# S3_CHAIR_SPKR-AMP_SPK.net
KiCad netlist of a schematic drawn in Altium Designer
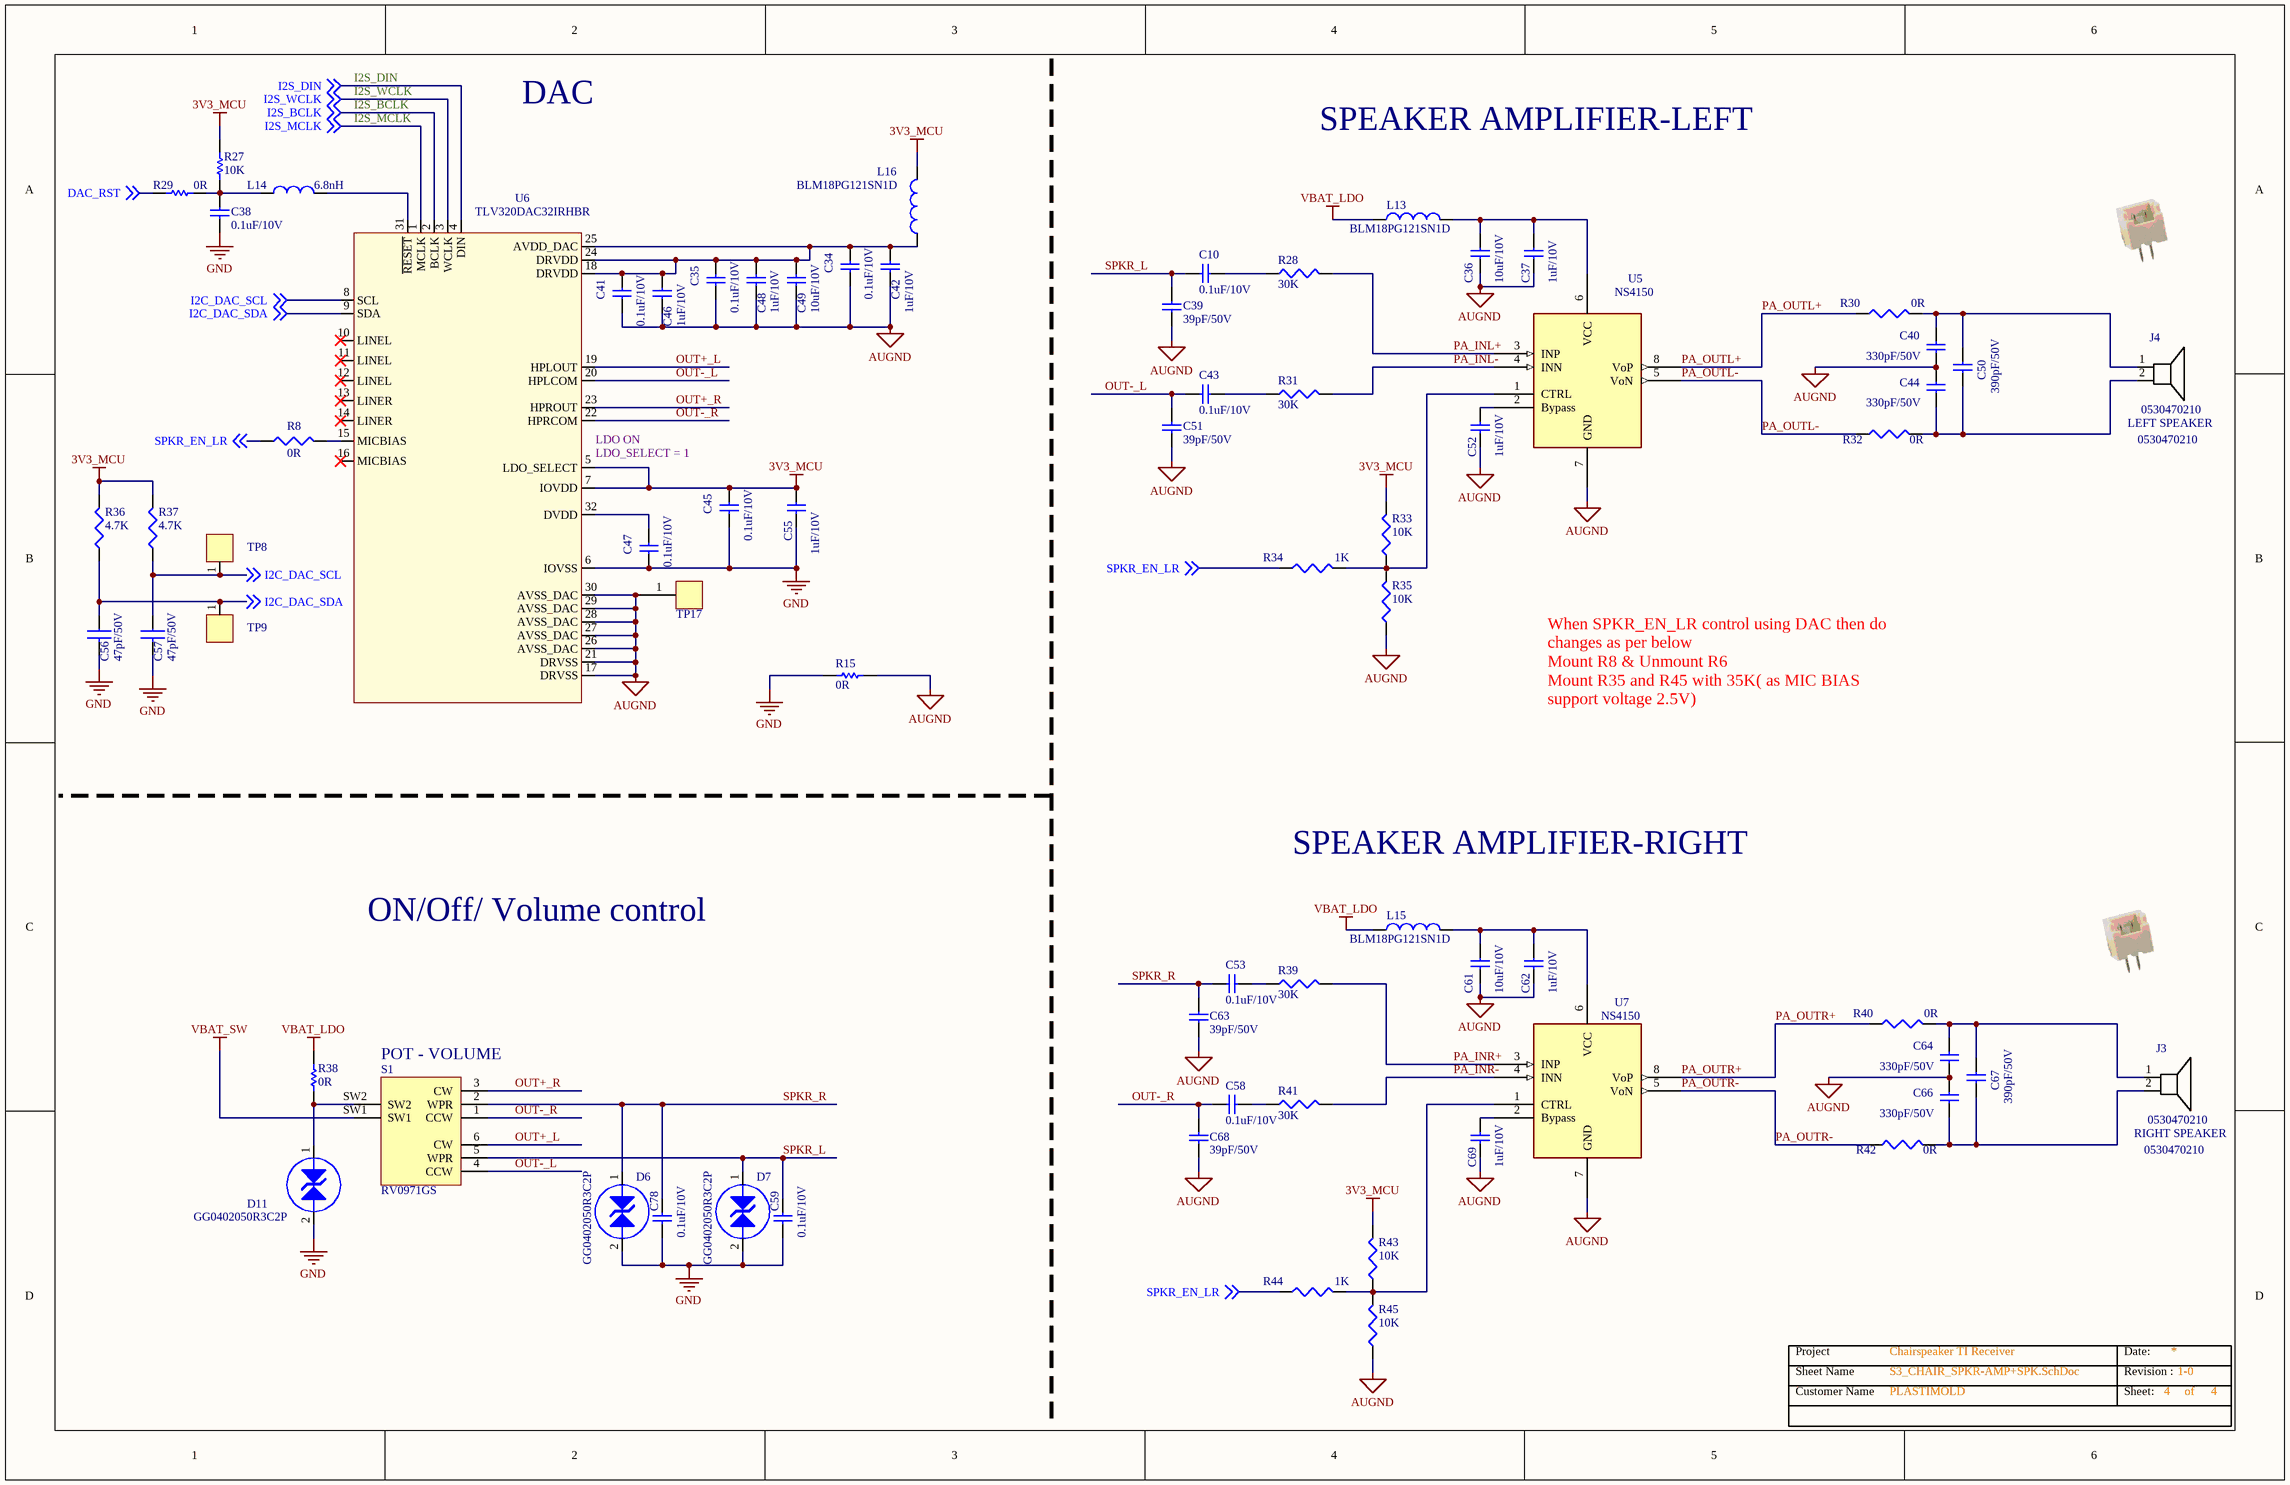
[diagram p0: S3_CHAIR_SPKR-AMP+SPK.SchDoc]

(export (version "E")
  (design (tool "Eeschema 10.0.6"))
  (components
    (comp (ref "C10")
      (value "0.1uF/10V")
      (footprint "CAP_0402_(M1005)")
      (description "=Description1")
      (libsource (lib "RC50_REV0-1_INT") (part "CAP_1"))
    )
    (comp (ref "C34")
      (value "0.1uF/10V")
      (footprint "CAP_0402_(M1005)")
      (description "=Description1")
      (libsource (lib "RC50_REV0-1_INT") (part "CAP_1"))
    )
    (comp (ref "C35")
      (value "0.1uF/10V")
      (footprint "CAP_0402_(M1005)")
      (description "=Description1")
      (libsource (lib "RC50_REV0-1_INT") (part "CAP_1"))
    )
    (comp (ref "C36")
      (value "10uF/10V")
      (footprint "CAP_0805_(M2012)")
      (description "=Description1")
      (libsource (lib "iTREE3") (part "CAP_10uF/16V_0805"))
    )
    (comp (ref "C37")
      (value "1uF/10V")
      (footprint "CAP_0402_(M1005)")
      (description "=Description1")
      (libsource (lib "iTREE3") (part "CAP_1uF/16v (10%)"))
    )
    (comp (ref "C38")
      (value "0.1uF/10V")
      (footprint "CAP_0402_(M1005)")
      (description "=Description1")
      (libsource (lib "RC50_REV0-1_INT") (part "CAP_1"))
    )
    (comp (ref "C39")
      (value "39pF/50V")
      (footprint "CAP_0402_(M1005)")
      (description "=Description1")
      (libsource (lib "iTREE3") (part "CAP_39pF/50V (±5%)"))
    )
    (comp (ref "C40")
      (value "330pF/50V")
      (footprint "CAP_0402_(M1005)")
      (description "=Description1")
      (libsource (lib "iTREE3") (part "CAP_330pF/50V (5%)"))
    )
    (comp (ref "C41")
      (value "0.1uF/10V")
      (footprint "CAP_0402_(M1005)")
      (description "=Description1")
      (libsource (lib "RC50_REV0-1_INT") (part "CAP_1"))
    )
    (comp (ref "C42")
      (value "1uF/10V")
      (footprint "CAP_0402_(M1005)")
      (description "=Description1")
      (libsource (lib "iTREE3") (part "CAP_1uF/16v (10%)"))
    )
    (comp (ref "C43")
      (value "0.1uF/10V")
      (footprint "CAP_0402_(M1005)")
      (description "=Description1")
      (libsource (lib "RC50_REV0-1_INT") (part "CAP_1"))
    )
    (comp (ref "C44")
      (value "330pF/50V")
      (footprint "CAP_0402_(M1005)")
      (description "=Description1")
      (libsource (lib "iTREE3") (part "CAP_330pF/50V (5%)"))
    )
    (comp (ref "C45")
      (value "0.1uF/10V")
      (footprint "CAP_0402_(M1005)")
      (description "=Description1")
      (libsource (lib "RC50_REV0-1_INT") (part "CAP_1"))
    )
    (comp (ref "C46")
      (value "1uF/10V")
      (footprint "CAP_0402_(M1005)")
      (description "=Description1")
      (libsource (lib "iTREE3") (part "CAP_1uF/16v (10%)"))
    )
    (comp (ref "C47")
      (value "0.1uF/10V")
      (footprint "CAP_0402_(M1005)")
      (description "=Description1")
      (libsource (lib "RC50_REV0-1_INT") (part "CAP_1"))
    )
    (comp (ref "C48")
      (value "1uF/10V")
      (footprint "CAP_0402_(M1005)")
      (description "=Description1")
      (libsource (lib "iTREE3") (part "CAP_1uF/16v (10%)"))
    )
    (comp (ref "C49")
      (value "10uF/10V")
      (footprint "CAP_0805_(M2012)")
      (description "=Description1")
      (libsource (lib "iTREE3") (part "CAP_10uF/16V_0805"))
    )
    (comp (ref "C50")
      (value "390pF/50V")
      (footprint "CAP_0402_(M1005)")
      (description "=Description1")
      (libsource (lib "iTREE3") (part "CAP_390pF/50V (5%)"))
    )
    (comp (ref "C51")
      (value "39pF/50V")
      (footprint "CAP_0402_(M1005)")
      (description "=Description1")
      (libsource (lib "iTREE3") (part "CAP_39pF/50V (±5%)"))
    )
    (comp (ref "C52")
      (value "1uF/10V")
      (footprint "CAP_0402_(M1005)")
      (description "=Description1")
      (libsource (lib "iTREE3") (part "CAP_1uF/16v (10%)"))
    )
    (comp (ref "C53")
      (value "0.1uF/10V")
      (footprint "CAP_0402_(M1005)")
      (description "=Description1")
      (libsource (lib "RC50_REV0-1_INT") (part "CAP_1"))
    )
    (comp (ref "C55")
      (value "1uF/10V")
      (footprint "CAP_0402_(M1005)")
      (description "=Description1")
      (libsource (lib "iTREE3") (part "CAP_1uF/16v (10%)"))
    )
    (comp (ref "C56")
      (value "47pF/50V")
      (footprint "CAP_0402_(M1005)")
      (description "=Description1")
      (libsource (lib "RC50_REV0-1") (part "CAP NP"))
    )
    (comp (ref "C57")
      (value "47pF/50V")
      (footprint "CAP_0402_(M1005)")
      (description "=Description1")
      (libsource (lib "RC50_REV0-1") (part "CAP NP"))
    )
    (comp (ref "C58")
      (value "0.1uF/10V")
      (footprint "CAP_0402_(M1005)")
      (description "=Description1")
      (libsource (lib "RC50_REV0-1_INT") (part "CAP_1"))
    )
    (comp (ref "C59")
      (value "0.1uF/10V")
      (footprint "CAP_0402_(M1005)")
      (description "=Description1")
      (libsource (lib "RC50_REV0-1_INT") (part "CAP_1"))
    )
    (comp (ref "C61")
      (value "10uF/10V")
      (footprint "CAP_0805_(M2012)")
      (description "=Description1")
      (libsource (lib "iTREE3") (part "CAP_10uF/16V_0805"))
    )
    (comp (ref "C62")
      (value "1uF/10V")
      (footprint "CAP_0402_(M1005)")
      (description "=Description1")
      (libsource (lib "iTREE3") (part "CAP_1uF/16v (10%)"))
    )
    (comp (ref "C63")
      (value "39pF/50V")
      (footprint "CAP_0402_(M1005)")
      (description "=Description1")
      (libsource (lib "iTREE3") (part "CAP_39pF/50V (±5%)"))
    )
    (comp (ref "C64")
      (value "330pF/50V")
      (footprint "CAP_0402_(M1005)")
      (description "=Description1")
      (libsource (lib "iTREE3") (part "CAP_330pF/50V (5%)"))
    )
    (comp (ref "C66")
      (value "330pF/50V")
      (footprint "CAP_0402_(M1005)")
      (description "=Description1")
      (libsource (lib "iTREE3") (part "CAP_330pF/50V (5%)"))
    )
    (comp (ref "C67")
      (value "390pF/50V")
      (footprint "CAP_0402_(M1005)")
      (description "=Description1")
      (libsource (lib "iTREE3") (part "CAP_390pF/50V (5%)"))
    )
    (comp (ref "C68")
      (value "39pF/50V")
      (footprint "CAP_0402_(M1005)")
      (description "=Description1")
      (libsource (lib "iTREE3") (part "CAP_39pF/50V (±5%)"))
    )
    (comp (ref "C69")
      (value "1uF/10V")
      (footprint "CAP_0402_(M1005)")
      (description "=Description1")
      (libsource (lib "iTREE3") (part "CAP_1uF/16v (10%)"))
    )
    (comp (ref "C78")
      (value "0.1uF/10V")
      (footprint "CAP_0402_(M1005)")
      (description "=Description1")
      (libsource (lib "RC50_REV0-1_INT") (part "CAP_1"))
    )
    (comp (ref "D6")
      (value "GG0402050R3C2P")
      (footprint "TVS_0402_(M1005)_BI-DIRECTIONAL")
      (description "=Description1")
      (libsource (lib "APC_SCH.") (part "TVS-DIODE"))
    )
    (comp (ref "D7")
      (value "GG0402050R3C2P")
      (footprint "TVS_0402_(M1005)_BI-DIRECTIONAL")
      (description "=Description1")
      (libsource (lib "APC_SCH.") (part "TVS-DIODE"))
    )
    (comp (ref "D11")
      (value "GG0402050R3C2P")
      (footprint "TVS_0402_(M1005)_BI-DIRECTIONAL")
      (description "=Description1")
      (libsource (lib "APC_SCH.") (part "TVS-DIODE"))
    )
    (comp (ref "J3")
      (value "0530470210")
      (footprint "0530470210")
      (description "=Description1")
      (fields (field (name "MANUFACTURER PART NUMBER 1") "0530470210"))
      (libsource (lib "iTREE3") (part "HDR1X2_speaker"))
    )
    (comp (ref "J4")
      (value "0530470210")
      (footprint "0530470210")
      (description "=Description1")
      (fields (field (name "MANUFACTURER PART NUMBER 1") "0530470210"))
      (libsource (lib "iTREE3") (part "HDR1X2_speaker"))
    )
    (comp (ref "L13")
      (value "BLM18PG121SN1D")
      (footprint "IND_0603_(M1608)")
      (description "=Description1")
      (fields (field (name "Comment") "BLM18PG181SN1D"))
      (libsource (lib "iTREE3") (part "BLM18PG181SN1D"))
    )
    (comp (ref "L14")
      (value "6.8nH")
      (footprint "IND_0402_(M1005)")
      (description "=Description1")
      (libsource (lib "Symbol") (part "IND"))
    )
    (comp (ref "L15")
      (value "BLM18PG121SN1D")
      (footprint "IND_0603_(M1608)")
      (description "=Description1")
      (fields (field (name "Comment") "BLM18PG181SN1D"))
      (libsource (lib "iTREE3") (part "BLM18PG181SN1D"))
    )
    (comp (ref "L16")
      (value "BLM18PG121SN1D")
      (footprint "IND_0603_(M1608)")
      (description "=Description1")
      (fields (field (name "Comment") "BLM18PG181SN1D"))
      (libsource (lib "iTREE3") (part "BLM18PG181SN1D"))
    )
    (comp (ref "R8")
      (value "0R")
      (footprint "RES_0402_(M1005)")
      (description "=Description1")
      (libsource (lib "iTREE3") (part "RES_0R"))
    )
    (comp (ref "R15")
      (value "0R")
      (footprint "RES_0402_(M1005)")
      (description "=Description1")
      (libsource (lib "RC50_REV0-1_INT") (part "RC1206JR-070RL"))
    )
    (comp (ref "R27")
      (value "10K")
      (footprint "RES_0402_(M1005)")
      (description "=Description1")
      (libsource (lib "Symbol") (part "RESISTOR"))
    )
    (comp (ref "R28")
      (value "30K")
      (footprint "RES_0402_(M1005)")
      (description "=Description1")
      (libsource (lib "iTREE3") (part "RES_30K_1%"))
    )
    (comp (ref "R29")
      (value "0R")
      (footprint "RES_0402_(M1005)")
      (description "=Description1")
      (libsource (lib "RC50_REV0-1_INT") (part "RC1206JR-070RL"))
    )
    (comp (ref "R30")
      (value "0R")
      (footprint "RES_0402_(M1005)")
      (description "=Description1")
      (libsource (lib "iTREE3") (part "RES_0R"))
    )
    (comp (ref "R31")
      (value "30K")
      (footprint "RES_0402_(M1005)")
      (description "=Description1")
      (libsource (lib "iTREE3") (part "RES_30K_1%"))
    )
    (comp (ref "R32")
      (value "0R")
      (footprint "RES_0402_(M1005)")
      (description "=Description1")
      (libsource (lib "iTREE3") (part "RES_0R"))
    )
    (comp (ref "R33")
      (value "10K")
      (footprint "RES_0402_(M1005)")
      (description "=Description1")
      (libsource (lib "iTREE3") (part "RES_10K_1%"))
    )
    (comp (ref "R34")
      (value "1K")
      (footprint "RES_0402_(M1005)")
      (description "=Description1")
      (libsource (lib "iTREE3") (part "RES_0R"))
    )
    (comp (ref "R35")
      (value "10K")
      (footprint "RES_0402_(M1005)")
      (description "=Description1")
      (libsource (lib "iTREE3") (part "RES_10K_1%"))
    )
    (comp (ref "R36")
      (value "4.7K")
      (footprint "RES_0402_(M1005)")
      (description "=Description1")
      (libsource (lib "APC_SCH") (part "RES"))
    )
    (comp (ref "R37")
      (value "4.7K")
      (footprint "RES_0402_(M1005)")
      (description "=Description1")
      (libsource (lib "APC_SCH") (part "RES"))
    )
    (comp (ref "R38")
      (value "0R")
      (footprint "RES_0402_(M1005)")
      (description "=Description1")
      (libsource (lib "RC50_REV0-1_INT") (part "RC1206JR-070RL"))
    )
    (comp (ref "R39")
      (value "30K")
      (footprint "RES_0402_(M1005)")
      (description "=Description1")
      (libsource (lib "iTREE3") (part "RES_30K_1%"))
    )
    (comp (ref "R40")
      (value "0R")
      (footprint "RES_0402_(M1005)")
      (description "=Description1")
      (libsource (lib "iTREE3") (part "RES_0R"))
    )
    (comp (ref "R41")
      (value "30K")
      (footprint "RES_0402_(M1005)")
      (description "=Description1")
      (libsource (lib "iTREE3") (part "RES_30K_1%"))
    )
    (comp (ref "R42")
      (value "0R")
      (footprint "RES_0402_(M1005)")
      (description "=Description1")
      (libsource (lib "iTREE3") (part "RES_0R"))
    )
    (comp (ref "R43")
      (value "10K")
      (footprint "RES_0402_(M1005)")
      (description "=Description1")
      (libsource (lib "iTREE3") (part "RES_10K_1%"))
    )
    (comp (ref "R44")
      (value "1K")
      (footprint "RES_0402_(M1005)")
      (description "=Description1")
      (libsource (lib "iTREE3") (part "RES_0R"))
    )
    (comp (ref "R45")
      (value "10K")
      (footprint "RES_0402_(M1005)")
      (description "=Description1")
      (libsource (lib "iTREE3") (part "RES_10K_1%"))
    )
    (comp (ref "S1")
      (value "RV0971GS")
      (footprint "RV0971GS")
      (description "=Description1")
      (libsource (lib "Symbol") (part "RV0971GS"))
    )
    (comp (ref "TP8")
      (value "TP")
      (footprint "TestP SM 30MIL ROUND")
      (description "=Description1")
      (libsource (lib "") (part "TP_1"))
    )
    (comp (ref "TP9")
      (value "TP")
      (footprint "TestP SM 30MIL ROUND")
      (description "=Description1")
      (libsource (lib "") (part "TP_2"))
    )
    (comp (ref "TP17")
      (value "TP")
      (footprint "TestP SM 30MIL ROUND")
      (description "=Description1")
      (libsource (lib "RC30 REv01") (part "TP"))
    )
    (comp (ref "U5")
      (value "NS4150")
      (footprint "SOP-8")
      (description "=Description1")
      (libsource (lib "iTREE3") (part "NS4150"))
    )
    (comp (ref "U6")
      (value "TLV320DAC32IRHBR")
      (footprint "VQFN32")
      (description "=Description1")
      (libsource (lib "Symbol") (part "TLV320DAC32"))
    )
    (comp (ref "U7")
      (value "NS4150")
      (footprint "SOP-8")
      (description "=Description1")
      (libsource (lib "iTREE3") (part "NS4150"))
    )
  )
  (nets
    (net (code "1") (name "/OUT+_L") (class "Default")
      (node (ref "S1") (pin "6") (pinfunction "CW_6") (pintype "passive"))
      (node (ref "U6") (pin "19") (pinfunction "HPLOUT_19") (pintype "passive"))
    )
    (net (code "2") (name "/OUT+_R") (class "Default")
      (node (ref "S1") (pin "3") (pinfunction "CW_3") (pintype "passive"))
      (node (ref "U6") (pin "23") (pinfunction "HPROUT_23") (pintype "passive"))
    )
    (net (code "3") (name "/OUT-_L") (class "Default")
      (node (ref "C43") (pin "1") (pinfunction "1_1") (pintype "passive"))
      (node (ref "C51") (pin "2") (pinfunction "2_2") (pintype "passive"))
      (node (ref "S1") (pin "4") (pinfunction "CCW_4") (pintype "passive"))
      (node (ref "U6") (pin "20") (pinfunction "HPLCOM_20") (pintype "passive"))
    )
    (net (code "4") (name "/OUT-_R") (class "Default")
      (node (ref "C58") (pin "1") (pinfunction "1_1") (pintype "passive"))
      (node (ref "C68") (pin "2") (pinfunction "2_2") (pintype "passive"))
      (node (ref "S1") (pin "1") (pinfunction "CCW_1") (pintype "passive"))
      (node (ref "U6") (pin "22") (pinfunction "HPRCOM_22") (pintype "passive"))
    )
    (net (code "5") (name "/PA_INL+") (class "Default")
      (node (ref "R28") (pin "1") (pintype "passive"))
      (node (ref "U5") (pin "3") (pinfunction "INP_3") (pintype "input"))
    )
    (net (code "6") (name "/PA_INL-") (class "Default")
      (node (ref "R31") (pin "1") (pintype "passive"))
      (node (ref "U5") (pin "4") (pinfunction "INN_4") (pintype "input"))
    )
    (net (code "7") (name "/PA_INR+") (class "Default")
      (node (ref "R39") (pin "1") (pintype "passive"))
      (node (ref "U7") (pin "3") (pinfunction "INP_3") (pintype "input"))
    )
    (net (code "8") (name "/PA_INR-") (class "Default")
      (node (ref "R41") (pin "1") (pintype "passive"))
      (node (ref "U7") (pin "4") (pinfunction "INN_4") (pintype "input"))
    )
    (net (code "9") (name "/PA_OUTL+") (class "Default")
      (node (ref "R30") (pin "1") (pintype "passive"))
      (node (ref "U5") (pin "8") (pinfunction "VoP_8") (pintype "output"))
    )
    (net (code "10") (name "/PA_OUTL-") (class "Default")
      (node (ref "R32") (pin "1") (pintype "passive"))
      (node (ref "U5") (pin "5") (pinfunction "VoN_5") (pintype "output"))
    )
    (net (code "11") (name "/PA_OUTR+") (class "Default")
      (node (ref "R40") (pin "1") (pintype "passive"))
      (node (ref "U7") (pin "8") (pinfunction "VoP_8") (pintype "output"))
    )
    (net (code "12") (name "/PA_OUTR-") (class "Default")
      (node (ref "R42") (pin "1") (pintype "passive"))
      (node (ref "U7") (pin "5") (pinfunction "VoN_5") (pintype "output"))
    )
    (net (code "13") (name "/SPKR_L") (class "Default")
      (node (ref "C10") (pin "1") (pinfunction "1_1") (pintype "passive"))
      (node (ref "C39") (pin "2") (pinfunction "2_2") (pintype "passive"))
      (node (ref "C59") (pin "2") (pinfunction "2_2") (pintype "passive"))
      (node (ref "D7") (pin "1") (pintype "passive"))
      (node (ref "S1") (pin "5") (pinfunction "WPR_5") (pintype "passive"))
    )
    (net (code "14") (name "/SPKR_R") (class "Default")
      (node (ref "C53") (pin "1") (pinfunction "1_1") (pintype "passive"))
      (node (ref "C63") (pin "2") (pinfunction "2_2") (pintype "passive"))
      (node (ref "C78") (pin "2") (pinfunction "2_2") (pintype "passive"))
      (node (ref "D6") (pin "1") (pintype "passive"))
      (node (ref "S1") (pin "2") (pinfunction "WPR_2") (pintype "passive"))
    )
    (net (code "15") (name "3V3_MCU") (class "Default")
      (node (ref "C45") (pin "2") (pinfunction "2_2") (pintype "passive"))
      (node (ref "C55") (pin "2") (pinfunction "2_2") (pintype "passive"))
      (node (ref "L16") (pin "2") (pinfunction "2_2") (pintype "passive"))
      (node (ref "R27") (pin "1") (pinfunction "1_1") (pintype "passive"))
      (node (ref "R33") (pin "2") (pintype "passive"))
      (node (ref "R36") (pin "2") (pintype "passive"))
      (node (ref "R37") (pin "2") (pintype "passive"))
      (node (ref "R43") (pin "2") (pintype "passive"))
      (node (ref "U6") (pin "5") (pinfunction "LDO_SELECT_5") (pintype "passive"))
      (node (ref "U6") (pin "7") (pinfunction "IOVDD_7") (pintype "passive"))
    )
    (net (code "16") (name "AUGND") (class "Default")
      (node (ref "C34") (pin "1") (pinfunction "1_1") (pintype "passive"))
      (node (ref "C35") (pin "1") (pinfunction "1_1") (pintype "passive"))
      (node (ref "C36") (pin "1") (pinfunction "1_1") (pintype "passive"))
      (node (ref "C37") (pin "1") (pinfunction "1_1") (pintype "passive"))
      (node (ref "C39") (pin "1") (pinfunction "1_1") (pintype "passive"))
      (node (ref "C40") (pin "1") (pinfunction "1_1") (pintype "passive"))
      (node (ref "C41") (pin "1") (pinfunction "1_1") (pintype "passive"))
      (node (ref "C42") (pin "1") (pinfunction "1_1") (pintype "passive"))
      (node (ref "C44") (pin "2") (pinfunction "2_2") (pintype "passive"))
      (node (ref "C46") (pin "1") (pinfunction "1_1") (pintype "passive"))
      (node (ref "C48") (pin "1") (pinfunction "1_1") (pintype "passive"))
      (node (ref "C49") (pin "1") (pinfunction "1_1") (pintype "passive"))
      (node (ref "C51") (pin "1") (pinfunction "1_1") (pintype "passive"))
      (node (ref "C52") (pin "1") (pinfunction "1_1") (pintype "passive"))
      (node (ref "C61") (pin "1") (pinfunction "1_1") (pintype "passive"))
      (node (ref "C62") (pin "1") (pinfunction "1_1") (pintype "passive"))
      (node (ref "C63") (pin "1") (pinfunction "1_1") (pintype "passive"))
      (node (ref "C64") (pin "1") (pinfunction "1_1") (pintype "passive"))
      (node (ref "C66") (pin "2") (pinfunction "2_2") (pintype "passive"))
      (node (ref "C68") (pin "1") (pinfunction "1_1") (pintype "passive"))
      (node (ref "C69") (pin "1") (pinfunction "1_1") (pintype "passive"))
      (node (ref "R15") (pin "1") (pinfunction "1_1") (pintype "passive"))
      (node (ref "R35") (pin "1") (pintype "passive"))
      (node (ref "R45") (pin "1") (pintype "passive"))
      (node (ref "TP17") (pin "1") (pintype "passive"))
      (node (ref "U5") (pin "7") (pinfunction "GND_7") (pintype "power_in"))
      (node (ref "U6") (pin "17") (pinfunction "DRVSS_17") (pintype "passive"))
      (node (ref "U6") (pin "21") (pinfunction "DRVSS_21") (pintype "passive"))
      (node (ref "U6") (pin "26") (pinfunction "AVSS_DAC_26") (pintype "passive"))
      (node (ref "U6") (pin "27") (pinfunction "AVSS_DAC_27") (pintype "passive"))
      (node (ref "U6") (pin "28") (pinfunction "AVSS_DAC_28") (pintype "passive"))
      (node (ref "U6") (pin "29") (pinfunction "AVSS_DAC_29") (pintype "passive"))
      (node (ref "U6") (pin "30") (pinfunction "AVSS_DAC_30") (pintype "passive"))
      (node (ref "U7") (pin "7") (pinfunction "GND_7") (pintype "power_in"))
    )
    (net (code "17") (name "DAC_RST") (class "Default")
      (node (ref "R29") (pin "1") (pinfunction "1_1") (pintype "passive"))
    )
    (net (code "18") (name "GND") (class "Default")
      (node (ref "C38") (pin "1") (pinfunction "1_1") (pintype "passive"))
      (node (ref "C45") (pin "1") (pinfunction "1_1") (pintype "passive"))
      (node (ref "C47") (pin "1") (pinfunction "1_1") (pintype "passive"))
      (node (ref "C55") (pin "1") (pinfunction "1_1") (pintype "passive"))
      (node (ref "C56") (pin "2") (pinfunction "2_2") (pintype "passive"))
      (node (ref "C57") (pin "2") (pinfunction "2_2") (pintype "passive"))
      (node (ref "C59") (pin "1") (pinfunction "1_1") (pintype "passive"))
      (node (ref "C78") (pin "1") (pinfunction "1_1") (pintype "passive"))
      (node (ref "D11") (pin "2") (pintype "passive"))
      (node (ref "D6") (pin "2") (pintype "passive"))
      (node (ref "D7") (pin "2") (pintype "passive"))
      (node (ref "R15") (pin "2") (pinfunction "2_2") (pintype "passive"))
      (node (ref "U6") (pin "6") (pinfunction "IOVSS_6") (pintype "passive"))
    )
    (net (code "19") (name "I2C_DAC_SCL") (class "Default")
      (node (ref "C57") (pin "1") (pinfunction "1_1") (pintype "passive"))
      (node (ref "R37") (pin "1") (pintype "passive"))
      (node (ref "TP8") (pin "1") (pintype "passive"))
      (node (ref "U6") (pin "8") (pinfunction "SCL_8") (pintype "passive"))
    )
    (net (code "20") (name "I2C_DAC_SDA") (class "Default")
      (node (ref "C56") (pin "1") (pinfunction "1_1") (pintype "passive"))
      (node (ref "R36") (pin "1") (pintype "passive"))
      (node (ref "TP9") (pin "1") (pintype "passive"))
      (node (ref "U6") (pin "9") (pinfunction "SDA_9") (pintype "passive"))
    )
    (net (code "21") (name "I2S_BCLK") (class "Default")
      (node (ref "U6") (pin "2") (pinfunction "BCLK_2") (pintype "passive"))
    )
    (net (code "22") (name "I2S_DIN") (class "Default")
      (node (ref "U6") (pin "4") (pinfunction "DIN_4") (pintype "passive"))
    )
    (net (code "23") (name "I2S_MCLK") (class "Default")
      (node (ref "U6") (pin "1") (pinfunction "MCLK_1") (pintype "passive"))
    )
    (net (code "24") (name "I2S_WCLK") (class "Default")
      (node (ref "U6") (pin "3") (pinfunction "WCLK_3") (pintype "passive"))
    )
    (net (code "25") (name "Net-(C10-Pad2)") (class "Default")
      (node (ref "C10") (pin "2") (pinfunction "2_2") (pintype "passive"))
      (node (ref "R28") (pin "2") (pintype "passive"))
    )
    (net (code "26") (name "Net-(C38-Pad2)") (class "Default")
      (node (ref "C38") (pin "2") (pinfunction "2_2") (pintype "passive"))
      (node (ref "L14") (pin "1") (pinfunction "1_1") (pintype "passive"))
      (node (ref "R27") (pin "2") (pinfunction "2_2") (pintype "passive"))
      (node (ref "R29") (pin "2") (pinfunction "2_2") (pintype "passive"))
    )
    (net (code "27") (name "Net-(C43-Pad2)") (class "Default")
      (node (ref "C43") (pin "2") (pinfunction "2_2") (pintype "passive"))
      (node (ref "R31") (pin "2") (pintype "passive"))
    )
    (net (code "28") (name "Net-(C53-Pad2)") (class "Default")
      (node (ref "C53") (pin "2") (pinfunction "2_2") (pintype "passive"))
      (node (ref "R39") (pin "2") (pintype "passive"))
    )
    (net (code "29") (name "Net-(C58-Pad2)") (class "Default")
      (node (ref "C58") (pin "2") (pinfunction "2_2") (pintype "passive"))
      (node (ref "R41") (pin "2") (pintype "passive"))
    )
    (net (code "30") (name "Net-(D11-Pad1)") (class "Default")
      (node (ref "D11") (pin "1") (pintype "passive"))
      (node (ref "R38") (pin "1") (pinfunction "1_1") (pintype "passive"))
      (node (ref "S1") (pin "SW2") (pinfunction "SW2_SW2") (pintype "passive"))
    )
    (net (code "31") (name "Net-(J3-NEG)") (class "Default")
      (node (ref "C66") (pin "1") (pinfunction "1_1") (pintype "passive"))
      (node (ref "C67") (pin "1") (pinfunction "1_1") (pintype "passive"))
      (node (ref "J3") (pin "2") (pinfunction "NEG_2") (pintype "passive"))
      (node (ref "R42") (pin "2") (pintype "passive"))
    )
    (net (code "32") (name "Net-(J3-POS)") (class "Default")
      (node (ref "C64") (pin "2") (pinfunction "2_2") (pintype "passive"))
      (node (ref "C67") (pin "2") (pinfunction "2_2") (pintype "passive"))
      (node (ref "J3") (pin "1") (pinfunction "POS_1") (pintype "passive"))
      (node (ref "R40") (pin "2") (pintype "passive"))
    )
    (net (code "33") (name "Net-(J4-NEG)") (class "Default")
      (node (ref "C44") (pin "1") (pinfunction "1_1") (pintype "passive"))
      (node (ref "C50") (pin "1") (pinfunction "1_1") (pintype "passive"))
      (node (ref "J4") (pin "2") (pinfunction "NEG_2") (pintype "passive"))
      (node (ref "R32") (pin "2") (pintype "passive"))
    )
    (net (code "34") (name "Net-(J4-POS)") (class "Default")
      (node (ref "C40") (pin "2") (pinfunction "2_2") (pintype "passive"))
      (node (ref "C50") (pin "2") (pinfunction "2_2") (pintype "passive"))
      (node (ref "J4") (pin "1") (pinfunction "POS_1") (pintype "passive"))
      (node (ref "R30") (pin "2") (pintype "passive"))
    )
    (net (code "35") (name "Net-(R8-Pad2)") (class "Default")
      (node (ref "R8") (pin "2") (pintype "passive"))
      (node (ref "U6") (pin "15") (pinfunction "MICBIAS_15") (pintype "passive"))
    )
    (net (code "36") (name "Net-(U5-Bypass)") (class "Default")
      (node (ref "C52") (pin "2") (pinfunction "2_2") (pintype "passive"))
      (node (ref "U5") (pin "2") (pinfunction "Bypass_2") (pintype "power_in"))
    )
    (net (code "37") (name "Net-(U5-CTRL)") (class "Default")
      (node (ref "R33") (pin "1") (pintype "passive"))
      (node (ref "R34") (pin "2") (pintype "passive"))
      (node (ref "R35") (pin "2") (pintype "passive"))
      (node (ref "U5") (pin "1") (pinfunction "CTRL_1") (pintype "passive"))
    )
    (net (code "38") (name "Net-(U5-VCC)") (class "Default")
      (node (ref "C36") (pin "2") (pinfunction "2_2") (pintype "passive"))
      (node (ref "C37") (pin "2") (pinfunction "2_2") (pintype "passive"))
      (node (ref "L13") (pin "2") (pinfunction "2_2") (pintype "passive"))
      (node (ref "U5") (pin "6") (pinfunction "VCC_6") (pintype "power_in"))
    )
    (net (code "39") (name "Net-(U6-AVDD_DAC)") (class "Default")
      (node (ref "C34") (pin "2") (pinfunction "2_2") (pintype "passive"))
      (node (ref "C35") (pin "2") (pinfunction "2_2") (pintype "passive"))
      (node (ref "C41") (pin "2") (pinfunction "2_2") (pintype "passive"))
      (node (ref "C42") (pin "2") (pinfunction "2_2") (pintype "passive"))
      (node (ref "C46") (pin "2") (pinfunction "2_2") (pintype "passive"))
      (node (ref "C48") (pin "2") (pinfunction "2_2") (pintype "passive"))
      (node (ref "C49") (pin "2") (pinfunction "2_2") (pintype "passive"))
      (node (ref "L16") (pin "1") (pinfunction "1_1") (pintype "passive"))
      (node (ref "U6") (pin "18") (pinfunction "DRVDD_18") (pintype "passive"))
      (node (ref "U6") (pin "24") (pinfunction "DRVDD_24") (pintype "passive"))
      (node (ref "U6") (pin "25") (pinfunction "AVDD_DAC_25") (pintype "passive"))
    )
    (net (code "40") (name "Net-(U6-DVDD)") (class "Default")
      (node (ref "C47") (pin "2") (pinfunction "2_2") (pintype "passive"))
      (node (ref "U6") (pin "32") (pinfunction "DVDD_32") (pintype "passive"))
    )
    (net (code "41") (name "Net-(U6-~{RESET})") (class "Default")
      (node (ref "L14") (pin "2") (pinfunction "2_2") (pintype "passive"))
      (node (ref "U6") (pin "31") (pinfunction "~{RESET}_31") (pintype "passive"))
    )
    (net (code "42") (name "Net-(U7-Bypass)") (class "Default")
      (node (ref "C69") (pin "2") (pinfunction "2_2") (pintype "passive"))
      (node (ref "U7") (pin "2") (pinfunction "Bypass_2") (pintype "power_in"))
    )
    (net (code "43") (name "Net-(U7-CTRL)") (class "Default")
      (node (ref "R43") (pin "1") (pintype "passive"))
      (node (ref "R44") (pin "2") (pintype "passive"))
      (node (ref "R45") (pin "2") (pintype "passive"))
      (node (ref "U7") (pin "1") (pinfunction "CTRL_1") (pintype "passive"))
    )
    (net (code "44") (name "Net-(U7-VCC)") (class "Default")
      (node (ref "C61") (pin "2") (pinfunction "2_2") (pintype "passive"))
      (node (ref "C62") (pin "2") (pinfunction "2_2") (pintype "passive"))
      (node (ref "L15") (pin "2") (pinfunction "2_2") (pintype "passive"))
      (node (ref "U7") (pin "6") (pinfunction "VCC_6") (pintype "power_in"))
    )
    (net (code "45") (name "SPKR_EN_LR") (class "Default")
      (node (ref "R34") (pin "1") (pintype "passive"))
      (node (ref "R44") (pin "1") (pintype "passive"))
      (node (ref "R8") (pin "1") (pintype "passive"))
    )
    (net (code "46") (name "VBAT_LDO") (class "Default")
      (node (ref "L13") (pin "1") (pinfunction "1_1") (pintype "passive"))
      (node (ref "L15") (pin "1") (pinfunction "1_1") (pintype "passive"))
      (node (ref "R38") (pin "2") (pinfunction "2_2") (pintype "passive"))
    )
    (net (code "47") (name "VBAT_SW") (class "Default")
      (node (ref "S1") (pin "SW1") (pinfunction "SW1_SW1") (pintype "passive"))
    )
    (net (code "48") (name "unconnected-(U6-LINEL-Pad10)") (class "Default")
      (node (ref "U6") (pin "10") (pinfunction "LINEL_10") (pintype "passive+no_connect"))
    )
    (net (code "49") (name "unconnected-(U6-LINEL-Pad11)") (class "Default")
      (node (ref "U6") (pin "11") (pinfunction "LINEL_11") (pintype "passive+no_connect"))
    )
    (net (code "50") (name "unconnected-(U6-LINEL-Pad12)") (class "Default")
      (node (ref "U6") (pin "12") (pinfunction "LINEL_12") (pintype "passive+no_connect"))
    )
    (net (code "51") (name "unconnected-(U6-LINER-Pad13)") (class "Default")
      (node (ref "U6") (pin "13") (pinfunction "LINER_13") (pintype "passive+no_connect"))
    )
    (net (code "52") (name "unconnected-(U6-LINER-Pad14)") (class "Default")
      (node (ref "U6") (pin "14") (pinfunction "LINER_14") (pintype "passive+no_connect"))
    )
    (net (code "53") (name "unconnected-(U6-MICBIAS-Pad16)") (class "Default")
      (node (ref "U6") (pin "16") (pinfunction "MICBIAS_16") (pintype "passive+no_connect"))
    )
  )
)
